# PangandaranV4.net
KiCad netlist of a schematic drawn in EAGLE
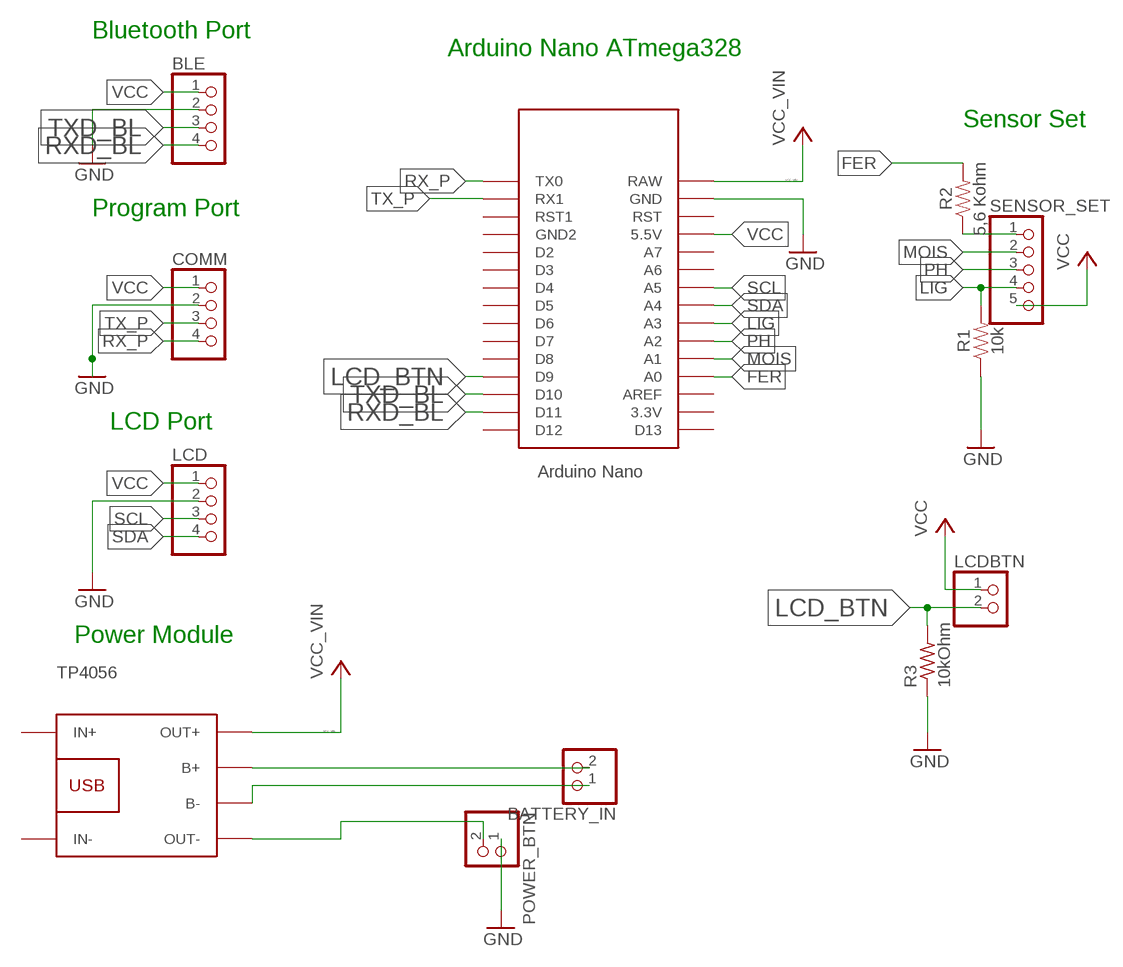
[diagram p0: schematic, sheet 1]

(export (version "E")
  (design (tool "Eeschema 10.0.6"))
  (components
    (comp (ref "BATTERY_IN")
      (value "PINHD-1X2")
      (footprint "eagle-import:1X02")
      (libsource (lib "eagle-import") (part "PINHD-1X2"))
    )
    (comp (ref "BLE")
      (value "PINHD-1X4")
      (footprint "eagle-import:1X04")
      (libsource (lib "eagle-import") (part "PINHD-1X4"))
    )
    (comp (ref "COMM")
      (value "PINHD-1X4")
      (footprint "eagle-import:1X04")
      (libsource (lib "eagle-import") (part "PINHD-1X4"))
    )
    (comp (ref "LCD")
      (value "PINHD-1X4")
      (footprint "eagle-import:1X04")
      (libsource (lib "eagle-import") (part "PINHD-1X4"))
    )
    (comp (ref "LCDBTN")
      (value "PINHD-1X2")
      (footprint "eagle-import:1X02")
      (libsource (lib "eagle-import") (part "PINHD-1X2"))
    )
    (comp (ref "POWER_BTN")
      (value "PINHD-1X2")
      (footprint "eagle-import:1X02")
      (libsource (lib "eagle-import") (part "PINHD-1X2"))
    )
    (comp (ref "R1")
      (value "10k")
      (footprint "eagle-import:0603")
      (libsource (lib "eagle-import") (part "1KOHM-0603-1/10W-1%"))
    )
    (comp (ref "R2")
      (value "5,6 Kohm")
      (footprint "eagle-import:0603")
      (libsource (lib "eagle-import") (part "0OHM-0603-1/10W-5%"))
    )
    (comp (ref "R3")
      (value "10kOhm")
      (footprint "eagle-import:M1206")
      (libsource (lib "eagle-import") (part "R-US_M1206"))
    )
    (comp (ref "SENSOR_SET")
      (value "PINHD-1X5")
      (footprint "eagle-import:1X05")
      (libsource (lib "eagle-import") (part "PINHD-1X5"))
    )
    (comp (ref "TP4056")
      (value "BATTERY-CHARGER-LI-PROT")
      (footprint "eagle-import:BATTERY-CHARGER-LI-PROT")
      (libsource (lib "eagle-import") (part "BATTERY-CHARGER-LI-PROT"))
    )
    (comp (ref "U$2")
      (value "NANO")
      (footprint "eagle-import:NANO")
      (libsource (lib "eagle-import") (part "NANO"))
    )
  )
  (nets
    (net (code "1") (name "FER") (class "Default")
      (node (ref "R2") (pin "2") (pinfunction "2_2") (pintype "passive"))
      (node (ref "U$2") (pin "A0") (pinfunction "A0_A0") (pintype "bidirectional"))
    )
    (net (code "2") (name "GND") (class "Default")
      (node (ref "BLE") (pin "2") (pinfunction "2_2") (pintype "passive"))
      (node (ref "COMM") (pin "2") (pinfunction "2_2") (pintype "passive"))
      (node (ref "LCD") (pin "2") (pinfunction "2_2") (pintype "passive"))
      (node (ref "POWER_BTN") (pin "1") (pinfunction "1_1") (pintype "passive"))
      (node (ref "R1") (pin "1") (pinfunction "1_1") (pintype "passive"))
      (node (ref "R3") (pin "1") (pinfunction "1_1") (pintype "passive"))
      (node (ref "U$2") (pin "GND") (pinfunction "GND_GND") (pintype "bidirectional"))
    )
    (net (code "3") (name "LCD_BTN") (class "Default")
      (node (ref "LCDBTN") (pin "2") (pinfunction "2_2") (pintype "passive"))
      (node (ref "R3") (pin "2") (pinfunction "2_2") (pintype "passive"))
      (node (ref "U$2") (pin "D9") (pinfunction "D9_D9") (pintype "bidirectional"))
    )
    (net (code "4") (name "LIG") (class "Default")
      (node (ref "R1") (pin "2") (pinfunction "2_2") (pintype "passive"))
      (node (ref "SENSOR_SET") (pin "4") (pinfunction "4_4") (pintype "passive"))
      (node (ref "U$2") (pin "A3") (pinfunction "A3_A3") (pintype "bidirectional"))
    )
    (net (code "5") (name "MOIS") (class "Default")
      (node (ref "SENSOR_SET") (pin "2") (pinfunction "2_2") (pintype "passive"))
      (node (ref "U$2") (pin "A1") (pinfunction "A1_A1") (pintype "bidirectional"))
    )
    (net (code "6") (name "Net-(BATTERY_IN-Pad1)") (class "Default")
      (node (ref "BATTERY_IN") (pin "1") (pinfunction "1_1") (pintype "passive"))
      (node (ref "TP4056") (pin "B-") (pinfunction "B-_B-") (pintype "bidirectional"))
    )
    (net (code "7") (name "Net-(BATTERY_IN-Pad2)") (class "Default")
      (node (ref "BATTERY_IN") (pin "2") (pinfunction "2_2") (pintype "passive"))
      (node (ref "TP4056") (pin "B+") (pinfunction "B+_B+") (pintype "bidirectional"))
    )
    (net (code "8") (name "Net-(POWER_BTN-Pad2)") (class "Default")
      (node (ref "POWER_BTN") (pin "2") (pinfunction "2_2") (pintype "passive"))
      (node (ref "TP4056") (pin "OUT-") (pinfunction "OUT-_OUT-") (pintype "bidirectional"))
    )
    (net (code "9") (name "Net-(R2-Pad1)") (class "Default")
      (node (ref "R2") (pin "1") (pinfunction "1_1") (pintype "passive"))
      (node (ref "SENSOR_SET") (pin "1") (pinfunction "1_1") (pintype "passive"))
    )
    (net (code "10") (name "PH") (class "Default")
      (node (ref "SENSOR_SET") (pin "3") (pinfunction "3_3") (pintype "passive"))
      (node (ref "U$2") (pin "A2") (pinfunction "A2_A2") (pintype "bidirectional"))
    )
    (net (code "11") (name "RXD_BL") (class "Default")
      (node (ref "BLE") (pin "4") (pinfunction "4_4") (pintype "passive"))
      (node (ref "U$2") (pin "D11") (pinfunction "D11_D11") (pintype "bidirectional"))
    )
    (net (code "12") (name "RX_P") (class "Default")
      (node (ref "COMM") (pin "4") (pinfunction "4_4") (pintype "passive"))
      (node (ref "U$2") (pin "TX0") (pinfunction "TX0_TX0") (pintype "bidirectional"))
    )
    (net (code "13") (name "SCL") (class "Default")
      (node (ref "LCD") (pin "3") (pinfunction "3_3") (pintype "passive"))
      (node (ref "U$2") (pin "A5") (pinfunction "A5_A5") (pintype "bidirectional"))
    )
    (net (code "14") (name "SDA") (class "Default")
      (node (ref "LCD") (pin "4") (pinfunction "4_4") (pintype "passive"))
      (node (ref "U$2") (pin "A4") (pinfunction "A4_A4") (pintype "bidirectional"))
    )
    (net (code "15") (name "TXD_BL") (class "Default")
      (node (ref "BLE") (pin "3") (pinfunction "3_3") (pintype "passive"))
      (node (ref "U$2") (pin "D10") (pinfunction "D10_D10") (pintype "bidirectional"))
    )
    (net (code "16") (name "TX_P") (class "Default")
      (node (ref "COMM") (pin "3") (pinfunction "3_3") (pintype "passive"))
      (node (ref "U$2") (pin "RX1") (pinfunction "RX1_RX1") (pintype "bidirectional"))
    )
    (net (code "17") (name "VCC") (class "Default")
      (node (ref "BLE") (pin "1") (pinfunction "1_1") (pintype "passive"))
      (node (ref "COMM") (pin "1") (pinfunction "1_1") (pintype "passive"))
      (node (ref "LCD") (pin "1") (pinfunction "1_1") (pintype "passive"))
      (node (ref "LCDBTN") (pin "1") (pinfunction "1_1") (pintype "passive"))
      (node (ref "SENSOR_SET") (pin "5") (pinfunction "5_5") (pintype "passive"))
      (node (ref "U$2") (pin "5V") (pinfunction "5.5V_5V") (pintype "bidirectional"))
    )
    (net (code "18") (name "VCC_VIN") (class "Default")
      (node (ref "TP4056") (pin "OUT+") (pinfunction "OUT+_OUT+") (pintype "bidirectional"))
      (node (ref "U$2") (pin "RAW") (pinfunction "RAW_RAW") (pintype "bidirectional"))
    )
    (net (code "19") (name "unconnected-(TP4056-PadIN+)") (class "Default")
      (node (ref "TP4056") (pin "IN+") (pinfunction "IN+_IN+") (pintype "bidirectional"))
    )
    (net (code "20") (name "unconnected-(TP4056-PadIN-)") (class "Default")
      (node (ref "TP4056") (pin "IN-") (pinfunction "IN-_IN-") (pintype "bidirectional"))
    )
    (net (code "21") (name "unconnected-(U$2-GND2-PadGND1)") (class "Default")
      (node (ref "U$2") (pin "GND1") (pinfunction "GND2_GND1") (pintype "bidirectional"))
    )
    (net (code "22") (name "unconnected-(U$2-Pad3.3V)") (class "Default")
      (node (ref "U$2") (pin "3.3V") (pinfunction "3.3V_3.3V") (pintype "bidirectional"))
    )
    (net (code "23") (name "unconnected-(U$2-PadA6)") (class "Default")
      (node (ref "U$2") (pin "A6") (pinfunction "A6_A6") (pintype "bidirectional"))
    )
    (net (code "24") (name "unconnected-(U$2-PadA7)") (class "Default")
      (node (ref "U$2") (pin "A7") (pinfunction "A7_A7") (pintype "bidirectional"))
    )
    (net (code "25") (name "unconnected-(U$2-PadAREF)") (class "Default")
      (node (ref "U$2") (pin "AREF") (pinfunction "AREF_AREF") (pintype "bidirectional"))
    )
    (net (code "26") (name "unconnected-(U$2-PadD2)") (class "Default")
      (node (ref "U$2") (pin "D2") (pinfunction "D2_D2") (pintype "bidirectional"))
    )
    (net (code "27") (name "unconnected-(U$2-PadD3)") (class "Default")
      (node (ref "U$2") (pin "D3") (pinfunction "D3_D3") (pintype "bidirectional"))
    )
    (net (code "28") (name "unconnected-(U$2-PadD4)") (class "Default")
      (node (ref "U$2") (pin "D4") (pinfunction "D4_D4") (pintype "bidirectional"))
    )
    (net (code "29") (name "unconnected-(U$2-PadD5)") (class "Default")
      (node (ref "U$2") (pin "D5") (pinfunction "D5_D5") (pintype "bidirectional"))
    )
    (net (code "30") (name "unconnected-(U$2-PadD6)") (class "Default")
      (node (ref "U$2") (pin "D6") (pinfunction "D6_D6") (pintype "bidirectional"))
    )
    (net (code "31") (name "unconnected-(U$2-PadD7)") (class "Default")
      (node (ref "U$2") (pin "D7") (pinfunction "D7_D7") (pintype "bidirectional"))
    )
    (net (code "32") (name "unconnected-(U$2-PadD8)") (class "Default")
      (node (ref "U$2") (pin "D8") (pinfunction "D8_D8") (pintype "bidirectional"))
    )
    (net (code "33") (name "unconnected-(U$2-PadD12)") (class "Default")
      (node (ref "U$2") (pin "D12") (pinfunction "D12_D12") (pintype "bidirectional"))
    )
    (net (code "34") (name "unconnected-(U$2-PadD13)") (class "Default")
      (node (ref "U$2") (pin "D13") (pinfunction "D13_D13") (pintype "bidirectional"))
    )
    (net (code "35") (name "unconnected-(U$2-PadICSP1)") (class "Default")
      (node (ref "U$2") (pin "ICSP1") (pinfunction "ICSP1_ICSP1") (pintype "bidirectional"))
    )
    (net (code "36") (name "unconnected-(U$2-PadICSP2)") (class "Default")
      (node (ref "U$2") (pin "ICSP2") (pinfunction "ICSP2_ICSP2") (pintype "bidirectional"))
    )
    (net (code "37") (name "unconnected-(U$2-PadICSP3)") (class "Default")
      (node (ref "U$2") (pin "ICSP3") (pinfunction "ICSP3_ICSP3") (pintype "bidirectional"))
    )
    (net (code "38") (name "unconnected-(U$2-PadICSP4)") (class "Default")
      (node (ref "U$2") (pin "ICSP4") (pinfunction "ICSP4_ICSP4") (pintype "bidirectional"))
    )
    (net (code "39") (name "unconnected-(U$2-PadICSP5)") (class "Default")
      (node (ref "U$2") (pin "ICSP5") (pinfunction "ICSP5_ICSP5") (pintype "bidirectional"))
    )
    (net (code "40") (name "unconnected-(U$2-PadICSP6)") (class "Default")
      (node (ref "U$2") (pin "ICSP6") (pinfunction "ICSP6_ICSP6") (pintype "bidirectional"))
    )
    (net (code "41") (name "unconnected-(U$2-PadRST)") (class "Default")
      (node (ref "U$2") (pin "RST") (pinfunction "RST_RST") (pintype "bidirectional"))
    )
    (net (code "42") (name "unconnected-(U$2-PadRST1)") (class "Default")
      (node (ref "U$2") (pin "RST1") (pinfunction "RST1_RST1") (pintype "bidirectional"))
    )
  )
)
